# panel2.net
KiCad netlist of a schematic drawn in EAGLE
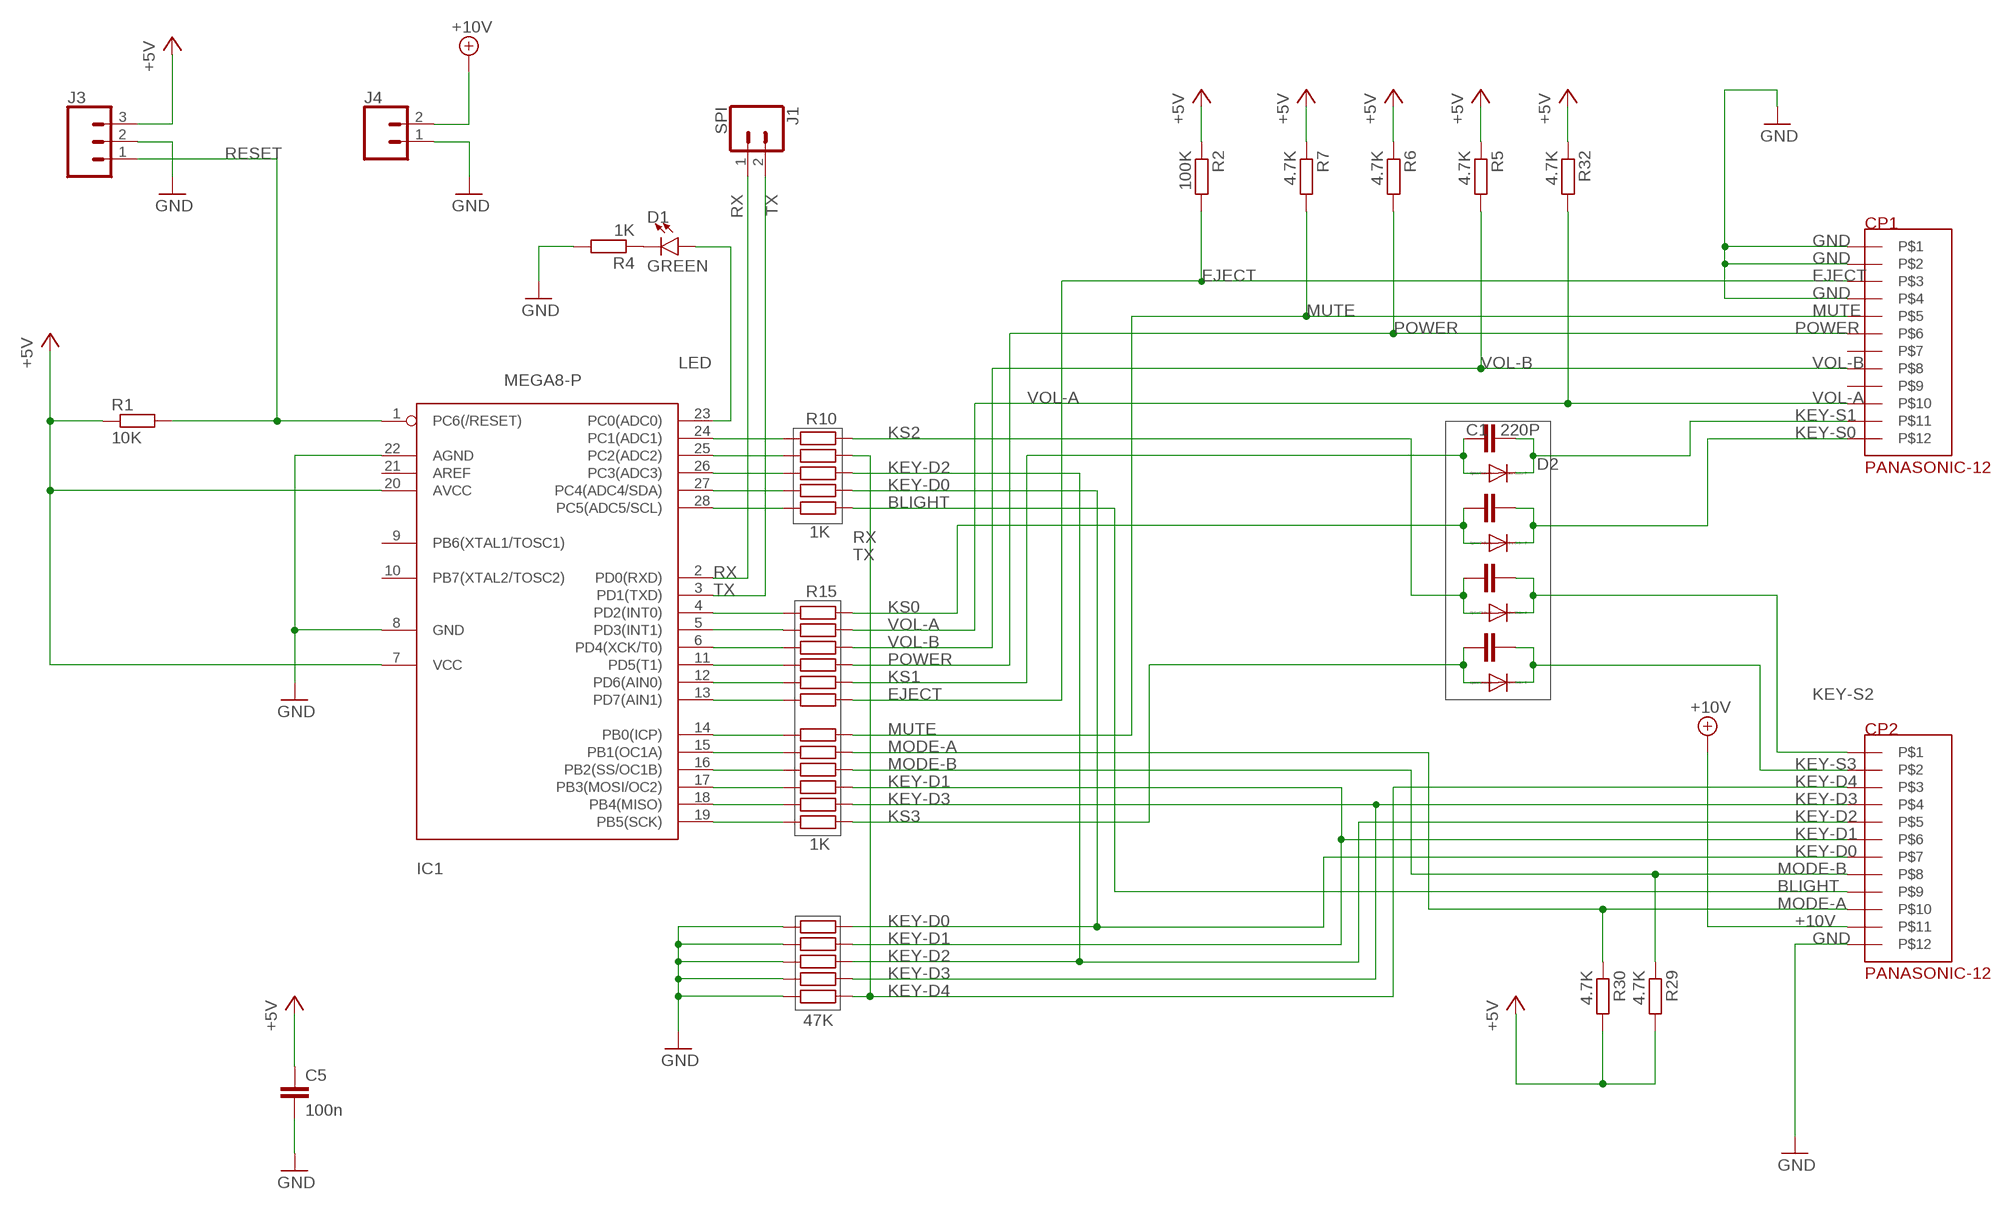
[diagram p0: schematic, sheet 1]

(export (version "E")
  (design (tool "Eeschema 10.0.6"))
  (components
    (comp (ref "C1")
      (value "220P")
      (footprint "eagle-import:C0805")
      (libsource (lib "eagle-import") (part "C-EUC0805"))
    )
    (comp (ref "C2")
      (value "220P")
      (footprint "eagle-import:C0805")
      (libsource (lib "eagle-import") (part "C-EUC0805"))
    )
    (comp (ref "C3")
      (value "220P")
      (footprint "eagle-import:C0805")
      (libsource (lib "eagle-import") (part "C-EUC0805"))
    )
    (comp (ref "C4")
      (value "220P")
      (footprint "eagle-import:C0805")
      (libsource (lib "eagle-import") (part "C-EUC0805"))
    )
    (comp (ref "C5")
      (value "100n")
      (footprint "eagle-import:C0805")
      (libsource (lib "eagle-import") (part "C-EUC0805"))
    )
    (comp (ref "CP1")
      (value "PANASONIC-12")
      (footprint "eagle-import:PANASONIC-12")
      (libsource (lib "eagle-import") (part "PANASONIC-12"))
    )
    (comp (ref "CP2")
      (value "PANASONIC-12")
      (footprint "eagle-import:PANASONIC-12")
      (libsource (lib "eagle-import") (part "PANASONIC-12"))
    )
    (comp (ref "D1")
      (value "GREEN")
      (footprint "eagle-import:LED-1206")
      (libsource (lib "eagle-import") (part "LED-GREEN1206"))
    )
    (comp (ref "D2")
      (value "1N4148DO35-10")
      (footprint "eagle-import:DO35-10")
      (libsource (lib "eagle-import") (part "1N4148DO35-10"))
    )
    (comp (ref "D3")
      (value "1N4148DO35-10")
      (footprint "eagle-import:DO35-10")
      (libsource (lib "eagle-import") (part "1N4148DO35-10"))
    )
    (comp (ref "D4")
      (value "1N4148DO35-10")
      (footprint "eagle-import:DO35-10")
      (libsource (lib "eagle-import") (part "1N4148DO35-10"))
    )
    (comp (ref "D5")
      (value "1N4148DO35-10")
      (footprint "eagle-import:DO35-10")
      (libsource (lib "eagle-import") (part "1N4148DO35-10"))
    )
    (comp (ref "IC1")
      (value "MEGA8-P")
      (footprint "eagle-import:DIL28-3")
      (libsource (lib "eagle-import") (part "MEGA8-P"))
    )
    (comp (ref "J1")
      (value "SPI")
      (footprint "eagle-import:1X02_LONGPADS")
      (libsource (lib "eagle-import") (part "CONN_02PTH3"))
    )
    (comp (ref "J3")
      (value "CONN_03LONGPADS")
      (footprint "eagle-import:1X03_LONGPADS")
      (libsource (lib "eagle-import") (part "CONN_03LONGPADS"))
    )
    (comp (ref "J4")
      (value "CONN_02LOCK_LONGPADS")
      (footprint "eagle-import:1X02_LOCK_LONGPADS")
      (libsource (lib "eagle-import") (part "CONN_02LOCK_LONGPADS"))
    )
    (comp (ref "R1")
      (value "10K")
      (footprint "eagle-import:M0805")
      (libsource (lib "eagle-import") (part "R-EU_M0805"))
    )
    (comp (ref "R2")
      (value "100K")
      (footprint "eagle-import:M0805")
      (libsource (lib "eagle-import") (part "R-EU_M0805"))
    )
    (comp (ref "R3")
      (value "47K")
      (footprint "eagle-import:0207_10")
      (libsource (lib "eagle-import") (part "R-EU_0207/10"))
    )
    (comp (ref "R4")
      (value "1K")
      (footprint "eagle-import:M0805")
      (libsource (lib "eagle-import") (part "R-EU_M0805"))
    )
    (comp (ref "R5")
      (value "4.7K")
      (footprint "eagle-import:M0805")
      (libsource (lib "eagle-import") (part "R-EU_M0805"))
    )
    (comp (ref "R6")
      (value "4.7K")
      (footprint "eagle-import:M0805")
      (libsource (lib "eagle-import") (part "R-EU_M0805"))
    )
    (comp (ref "R7")
      (value "4.7K")
      (footprint "eagle-import:M0805")
      (libsource (lib "eagle-import") (part "R-EU_M0805"))
    )
    (comp (ref "R8")
      (value "1K")
      (footprint "eagle-import:M0805")
      (libsource (lib "eagle-import") (part "R-EU_M0805"))
    )
    (comp (ref "R9")
      (value "1K")
      (footprint "eagle-import:M0805")
      (libsource (lib "eagle-import") (part "R-EU_M0805"))
    )
    (comp (ref "R10")
      (value "1K")
      (footprint "eagle-import:M0805")
      (libsource (lib "eagle-import") (part "R-EU_M0805"))
    )
    (comp (ref "R11")
      (value "1K")
      (footprint "eagle-import:M0805")
      (libsource (lib "eagle-import") (part "R-EU_M0805"))
    )
    (comp (ref "R12")
      (value "1K")
      (footprint "eagle-import:M0805")
      (libsource (lib "eagle-import") (part "R-EU_M0805"))
    )
    (comp (ref "R13")
      (value "1K")
      (footprint "eagle-import:M0805")
      (libsource (lib "eagle-import") (part "R-EU_M0805"))
    )
    (comp (ref "R14")
      (value "1K")
      (footprint "eagle-import:M0805")
      (libsource (lib "eagle-import") (part "R-EU_M0805"))
    )
    (comp (ref "R15")
      (value "1K")
      (footprint "eagle-import:M0805")
      (libsource (lib "eagle-import") (part "R-EU_M0805"))
    )
    (comp (ref "R16")
      (value "1K")
      (footprint "eagle-import:M0805")
      (libsource (lib "eagle-import") (part "R-EU_M0805"))
    )
    (comp (ref "R17")
      (value "1K")
      (footprint "eagle-import:M0805")
      (libsource (lib "eagle-import") (part "R-EU_M0805"))
    )
    (comp (ref "R18")
      (value "1K")
      (footprint "eagle-import:M0805")
      (libsource (lib "eagle-import") (part "R-EU_M0805"))
    )
    (comp (ref "R19")
      (value "1K")
      (footprint "eagle-import:M0805")
      (libsource (lib "eagle-import") (part "R-EU_M0805"))
    )
    (comp (ref "R20")
      (value "1K")
      (footprint "eagle-import:M0805")
      (libsource (lib "eagle-import") (part "R-EU_M0805"))
    )
    (comp (ref "R21")
      (value "1K")
      (footprint "eagle-import:M0805")
      (libsource (lib "eagle-import") (part "R-EU_M0805"))
    )
    (comp (ref "R22")
      (value "1K")
      (footprint "eagle-import:M0805")
      (libsource (lib "eagle-import") (part "R-EU_M0805"))
    )
    (comp (ref "R23")
      (value "1K")
      (footprint "eagle-import:M0805")
      (libsource (lib "eagle-import") (part "R-EU_M0805"))
    )
    (comp (ref "R24")
      (value "47K")
      (footprint "eagle-import:0207_10")
      (libsource (lib "eagle-import") (part "R-EU_0207/10"))
    )
    (comp (ref "R25")
      (value "47K")
      (footprint "eagle-import:0207_10")
      (libsource (lib "eagle-import") (part "R-EU_0207/10"))
    )
    (comp (ref "R28")
      (value "47K")
      (footprint "eagle-import:0207_10")
      (libsource (lib "eagle-import") (part "R-EU_0207/10"))
    )
    (comp (ref "R29")
      (value "4.7K")
      (footprint "eagle-import:M0805")
      (libsource (lib "eagle-import") (part "R-EU_M0805"))
    )
    (comp (ref "R30")
      (value "4.7K")
      (footprint "eagle-import:M0805")
      (libsource (lib "eagle-import") (part "R-EU_M0805"))
    )
    (comp (ref "R31")
      (value "1K")
      (footprint "eagle-import:M0805")
      (libsource (lib "eagle-import") (part "R-EU_M0805"))
    )
    (comp (ref "R32")
      (value "4.7K")
      (footprint "eagle-import:0207_10")
      (libsource (lib "eagle-import") (part "R-EU_0207/10"))
    )
    (comp (ref "R34")
      (value "47K")
      (footprint "eagle-import:0207_10")
      (libsource (lib "eagle-import") (part "R-EU_0207/10"))
    )
  )
  (nets
    (net (code "1") (name "+5V") (class "Default")
      (node (ref "C5") (pin "1") (pinfunction "1_1") (pintype "passive"))
      (node (ref "IC1") (pin "20") (pinfunction "AVCC_20") (pintype "bidirectional"))
      (node (ref "IC1") (pin "7") (pinfunction "VCC_7") (pintype "bidirectional"))
      (node (ref "J3") (pin "3") (pinfunction "3_3") (pintype "passive"))
      (node (ref "R1") (pin "1") (pinfunction "1_1") (pintype "passive"))
      (node (ref "R2") (pin "1") (pinfunction "1_1") (pintype "passive"))
      (node (ref "R29") (pin "2") (pinfunction "2_2") (pintype "passive"))
      (node (ref "R30") (pin "2") (pinfunction "2_2") (pintype "passive"))
      (node (ref "R32") (pin "1") (pinfunction "1_1") (pintype "passive"))
      (node (ref "R5") (pin "1") (pinfunction "1_1") (pintype "passive"))
      (node (ref "R6") (pin "1") (pinfunction "1_1") (pintype "passive"))
      (node (ref "R7") (pin "1") (pinfunction "1_1") (pintype "passive"))
    )
    (net (code "2") (name "+10V") (class "Default")
      (node (ref "CP2") (pin "P11") (pinfunction "P$11_P11") (pintype "bidirectional"))
      (node (ref "J4") (pin "2") (pinfunction "2_2") (pintype "passive"))
    )
    (net (code "3") (name "/BLIGHT") (class "Default")
      (node (ref "CP2") (pin "P9") (pinfunction "P$9_P9") (pintype "bidirectional"))
      (node (ref "R14") (pin "2") (pinfunction "2_2") (pintype "passive"))
    )
    (net (code "4") (name "/EJECT") (class "Default")
      (node (ref "CP1") (pin "P3") (pinfunction "P$3_P3") (pintype "bidirectional"))
      (node (ref "R2") (pin "2") (pinfunction "2_2") (pintype "passive"))
      (node (ref "R23") (pin "2") (pinfunction "2_2") (pintype "passive"))
    )
    (net (code "5") (name "/KEY-D0") (class "Default")
      (node (ref "CP2") (pin "P7") (pinfunction "P$7_P7") (pintype "bidirectional"))
      (node (ref "R13") (pin "2") (pinfunction "2_2") (pintype "passive"))
      (node (ref "R24") (pin "1") (pinfunction "1_1") (pintype "passive"))
    )
    (net (code "6") (name "/KEY-D1") (class "Default")
      (node (ref "CP2") (pin "P6") (pinfunction "P$6_P6") (pintype "bidirectional"))
      (node (ref "R18") (pin "2") (pinfunction "2_2") (pintype "passive"))
      (node (ref "R25") (pin "1") (pinfunction "1_1") (pintype "passive"))
    )
    (net (code "7") (name "/KEY-D2") (class "Default")
      (node (ref "CP2") (pin "P5") (pinfunction "P$5_P5") (pintype "bidirectional"))
      (node (ref "R12") (pin "2") (pinfunction "2_2") (pintype "passive"))
      (node (ref "R28") (pin "1") (pinfunction "1_1") (pintype "passive"))
    )
    (net (code "8") (name "/KEY-D3") (class "Default")
      (node (ref "CP2") (pin "P4") (pinfunction "P$4_P4") (pintype "bidirectional"))
      (node (ref "R21") (pin "2") (pinfunction "2_2") (pintype "passive"))
      (node (ref "R34") (pin "1") (pinfunction "1_1") (pintype "passive"))
    )
    (net (code "9") (name "/KEY-D4") (class "Default")
      (node (ref "CP2") (pin "P3") (pinfunction "P$3_P3") (pintype "bidirectional"))
      (node (ref "R11") (pin "2") (pinfunction "2_2") (pintype "passive"))
      (node (ref "R3") (pin "1") (pinfunction "1_1") (pintype "passive"))
    )
    (net (code "10") (name "/KEY-S0") (class "Default")
      (node (ref "C2") (pin "2") (pinfunction "2_2") (pintype "passive"))
      (node (ref "CP1") (pin "P12") (pinfunction "P$12_P12") (pintype "bidirectional"))
      (node (ref "D3") (pin "C") (pinfunction "C_C") (pintype "passive"))
    )
    (net (code "11") (name "/KEY-S1") (class "Default")
      (node (ref "C1") (pin "2") (pinfunction "2_2") (pintype "passive"))
      (node (ref "CP1") (pin "P11") (pinfunction "P$11_P11") (pintype "bidirectional"))
      (node (ref "D2") (pin "C") (pinfunction "C_C") (pintype "passive"))
    )
    (net (code "12") (name "/KEY-S2") (class "Default")
      (node (ref "C3") (pin "2") (pinfunction "2_2") (pintype "passive"))
      (node (ref "CP2") (pin "P1") (pinfunction "P$1_P1") (pintype "bidirectional"))
      (node (ref "D4") (pin "C") (pinfunction "C_C") (pintype "passive"))
    )
    (net (code "13") (name "/KEY-S3") (class "Default")
      (node (ref "C4") (pin "2") (pinfunction "2_2") (pintype "passive"))
      (node (ref "CP2") (pin "P2") (pinfunction "P$2_P2") (pintype "bidirectional"))
      (node (ref "D5") (pin "C") (pinfunction "C_C") (pintype "passive"))
    )
    (net (code "14") (name "/KS0") (class "Default")
      (node (ref "C2") (pin "1") (pinfunction "1_1") (pintype "passive"))
      (node (ref "D3") (pin "A") (pinfunction "A_A") (pintype "passive"))
      (node (ref "R15") (pin "2") (pinfunction "2_2") (pintype "passive"))
    )
    (net (code "15") (name "/KS1") (class "Default")
      (node (ref "C1") (pin "1") (pinfunction "1_1") (pintype "passive"))
      (node (ref "D2") (pin "A") (pinfunction "A_A") (pintype "passive"))
      (node (ref "R22") (pin "2") (pinfunction "2_2") (pintype "passive"))
    )
    (net (code "16") (name "/KS2") (class "Default")
      (node (ref "C3") (pin "1") (pinfunction "1_1") (pintype "passive"))
      (node (ref "D4") (pin "A") (pinfunction "A_A") (pintype "passive"))
      (node (ref "R10") (pin "2") (pinfunction "2_2") (pintype "passive"))
    )
    (net (code "17") (name "/KS3") (class "Default")
      (node (ref "C4") (pin "1") (pinfunction "1_1") (pintype "passive"))
      (node (ref "D5") (pin "A") (pinfunction "A_A") (pintype "passive"))
      (node (ref "R31") (pin "2") (pinfunction "2_2") (pintype "passive"))
    )
    (net (code "18") (name "/LED") (class "Default")
      (node (ref "D1") (pin "A") (pinfunction "A_A") (pintype "passive"))
      (node (ref "IC1") (pin "23") (pinfunction "PC0(ADC0)_23") (pintype "bidirectional"))
    )
    (net (code "19") (name "/MODE-A") (class "Default")
      (node (ref "CP2") (pin "P10") (pinfunction "P$10_P10") (pintype "bidirectional"))
      (node (ref "R20") (pin "2") (pinfunction "2_2") (pintype "passive"))
      (node (ref "R30") (pin "1") (pinfunction "1_1") (pintype "passive"))
    )
    (net (code "20") (name "/MODE-B") (class "Default")
      (node (ref "CP2") (pin "P8") (pinfunction "P$8_P8") (pintype "bidirectional"))
      (node (ref "R17") (pin "2") (pinfunction "2_2") (pintype "passive"))
      (node (ref "R29") (pin "1") (pinfunction "1_1") (pintype "passive"))
    )
    (net (code "21") (name "/MUTE") (class "Default")
      (node (ref "CP1") (pin "P5") (pinfunction "P$5_P5") (pintype "bidirectional"))
      (node (ref "R19") (pin "2") (pinfunction "2_2") (pintype "passive"))
      (node (ref "R7") (pin "2") (pinfunction "2_2") (pintype "passive"))
    )
    (net (code "22") (name "/POWER") (class "Default")
      (node (ref "CP1") (pin "P6") (pinfunction "P$6_P6") (pintype "bidirectional"))
      (node (ref "R6") (pin "2") (pinfunction "2_2") (pintype "passive"))
      (node (ref "R9") (pin "2") (pinfunction "2_2") (pintype "passive"))
    )
    (net (code "23") (name "/RESET") (class "Default")
      (node (ref "IC1") (pin "1") (pinfunction "PC6(/RESET)_1") (pintype "bidirectional"))
      (node (ref "J3") (pin "1") (pinfunction "1_1") (pintype "passive"))
      (node (ref "R1") (pin "2") (pinfunction "2_2") (pintype "passive"))
    )
    (net (code "24") (name "/RX") (class "Default")
      (node (ref "IC1") (pin "2") (pinfunction "PD0(RXD)_2") (pintype "bidirectional"))
      (node (ref "J1") (pin "1") (pinfunction "1_1") (pintype "passive"))
    )
    (net (code "25") (name "/TX") (class "Default")
      (node (ref "IC1") (pin "3") (pinfunction "PD1(TXD)_3") (pintype "bidirectional"))
      (node (ref "J1") (pin "2") (pinfunction "2_2") (pintype "passive"))
    )
    (net (code "26") (name "/VOL-A") (class "Default")
      (node (ref "CP1") (pin "P10") (pinfunction "P$10_P10") (pintype "bidirectional"))
      (node (ref "R16") (pin "2") (pinfunction "2_2") (pintype "passive"))
      (node (ref "R32") (pin "2") (pinfunction "2_2") (pintype "passive"))
    )
    (net (code "27") (name "/VOL-B") (class "Default")
      (node (ref "CP1") (pin "P8") (pinfunction "P$8_P8") (pintype "bidirectional"))
      (node (ref "R5") (pin "2") (pinfunction "2_2") (pintype "passive"))
      (node (ref "R8") (pin "2") (pinfunction "2_2") (pintype "passive"))
    )
    (net (code "28") (name "GND") (class "Default")
      (node (ref "C5") (pin "2") (pinfunction "2_2") (pintype "passive"))
      (node (ref "CP1") (pin "P1") (pinfunction "P$1_P1") (pintype "bidirectional"))
      (node (ref "CP1") (pin "P2") (pinfunction "P$2_P2") (pintype "bidirectional"))
      (node (ref "CP1") (pin "P4") (pinfunction "P$4_P4") (pintype "bidirectional"))
      (node (ref "CP2") (pin "P12") (pinfunction "P$12_P12") (pintype "bidirectional"))
      (node (ref "IC1") (pin "22") (pinfunction "AGND_22") (pintype "bidirectional"))
      (node (ref "IC1") (pin "8") (pinfunction "GND_8") (pintype "bidirectional"))
      (node (ref "J3") (pin "2") (pinfunction "2_2") (pintype "passive"))
      (node (ref "J4") (pin "1") (pinfunction "1_1") (pintype "passive"))
      (node (ref "R24") (pin "2") (pinfunction "2_2") (pintype "passive"))
      (node (ref "R25") (pin "2") (pinfunction "2_2") (pintype "passive"))
      (node (ref "R28") (pin "2") (pinfunction "2_2") (pintype "passive"))
      (node (ref "R3") (pin "2") (pinfunction "2_2") (pintype "passive"))
      (node (ref "R34") (pin "2") (pinfunction "2_2") (pintype "passive"))
      (node (ref "R4") (pin "2") (pinfunction "2_2") (pintype "passive"))
    )
    (net (code "29") (name "Net-(D1-PadC)") (class "Default")
      (node (ref "D1") (pin "C") (pinfunction "C_C") (pintype "passive"))
      (node (ref "R4") (pin "1") (pinfunction "1_1") (pintype "passive"))
    )
    (net (code "30") (name "Net-(IC1-PB0(ICP))") (class "Default")
      (node (ref "IC1") (pin "14") (pinfunction "PB0(ICP)_14") (pintype "bidirectional"))
      (node (ref "R19") (pin "1") (pinfunction "1_1") (pintype "passive"))
    )
    (net (code "31") (name "Net-(IC1-PB1(OC1A))") (class "Default")
      (node (ref "IC1") (pin "15") (pinfunction "PB1(OC1A)_15") (pintype "bidirectional"))
      (node (ref "R20") (pin "1") (pinfunction "1_1") (pintype "passive"))
    )
    (net (code "32") (name "Net-(IC1-PB2(SS{slash}OC1B))") (class "Default")
      (node (ref "IC1") (pin "16") (pinfunction "PB2(SS/OC1B)_16") (pintype "bidirectional"))
      (node (ref "R17") (pin "1") (pinfunction "1_1") (pintype "passive"))
    )
    (net (code "33") (name "Net-(IC1-PB3(MOSI{slash}OC2))") (class "Default")
      (node (ref "IC1") (pin "17") (pinfunction "PB3(MOSI/OC2)_17") (pintype "bidirectional"))
      (node (ref "R18") (pin "1") (pinfunction "1_1") (pintype "passive"))
    )
    (net (code "34") (name "Net-(IC1-PB4(MISO))") (class "Default")
      (node (ref "IC1") (pin "18") (pinfunction "PB4(MISO)_18") (pintype "bidirectional"))
      (node (ref "R21") (pin "1") (pinfunction "1_1") (pintype "passive"))
    )
    (net (code "35") (name "Net-(IC1-PB5(SCK))") (class "Default")
      (node (ref "IC1") (pin "19") (pinfunction "PB5(SCK)_19") (pintype "bidirectional"))
      (node (ref "R31") (pin "1") (pinfunction "1_1") (pintype "passive"))
    )
    (net (code "36") (name "Net-(IC1-PC1(ADC1))") (class "Default")
      (node (ref "IC1") (pin "24") (pinfunction "PC1(ADC1)_24") (pintype "bidirectional"))
      (node (ref "R10") (pin "1") (pinfunction "1_1") (pintype "passive"))
    )
    (net (code "37") (name "Net-(IC1-PC2(ADC2))") (class "Default")
      (node (ref "IC1") (pin "25") (pinfunction "PC2(ADC2)_25") (pintype "bidirectional"))
      (node (ref "R11") (pin "1") (pinfunction "1_1") (pintype "passive"))
    )
    (net (code "38") (name "Net-(IC1-PC3(ADC3))") (class "Default")
      (node (ref "IC1") (pin "26") (pinfunction "PC3(ADC3)_26") (pintype "bidirectional"))
      (node (ref "R12") (pin "1") (pinfunction "1_1") (pintype "passive"))
    )
    (net (code "39") (name "Net-(IC1-PC4(ADC4{slash}SDA))") (class "Default")
      (node (ref "IC1") (pin "27") (pinfunction "PC4(ADC4/SDA)_27") (pintype "bidirectional"))
      (node (ref "R13") (pin "1") (pinfunction "1_1") (pintype "passive"))
    )
    (net (code "40") (name "Net-(IC1-PC5(ADC5{slash}SCL))") (class "Default")
      (node (ref "IC1") (pin "28") (pinfunction "PC5(ADC5/SCL)_28") (pintype "bidirectional"))
      (node (ref "R14") (pin "1") (pinfunction "1_1") (pintype "passive"))
    )
    (net (code "41") (name "Net-(IC1-PD2(INT0))") (class "Default")
      (node (ref "IC1") (pin "4") (pinfunction "PD2(INT0)_4") (pintype "bidirectional"))
      (node (ref "R15") (pin "1") (pinfunction "1_1") (pintype "passive"))
    )
    (net (code "42") (name "Net-(IC1-PD3(INT1))") (class "Default")
      (node (ref "IC1") (pin "5") (pinfunction "PD3(INT1)_5") (pintype "bidirectional"))
      (node (ref "R16") (pin "1") (pinfunction "1_1") (pintype "passive"))
    )
    (net (code "43") (name "Net-(IC1-PD4(XCK{slash}T0))") (class "Default")
      (node (ref "IC1") (pin "6") (pinfunction "PD4(XCK/T0)_6") (pintype "bidirectional"))
      (node (ref "R8") (pin "1") (pinfunction "1_1") (pintype "passive"))
    )
    (net (code "44") (name "Net-(IC1-PD5(T1))") (class "Default")
      (node (ref "IC1") (pin "11") (pinfunction "PD5(T1)_11") (pintype "bidirectional"))
      (node (ref "R9") (pin "1") (pinfunction "1_1") (pintype "passive"))
    )
    (net (code "45") (name "Net-(IC1-PD6(AIN0))") (class "Default")
      (node (ref "IC1") (pin "12") (pinfunction "PD6(AIN0)_12") (pintype "bidirectional"))
      (node (ref "R22") (pin "1") (pinfunction "1_1") (pintype "passive"))
    )
    (net (code "46") (name "Net-(IC1-PD7(AIN1))") (class "Default")
      (node (ref "IC1") (pin "13") (pinfunction "PD7(AIN1)_13") (pintype "bidirectional"))
      (node (ref "R23") (pin "1") (pinfunction "1_1") (pintype "passive"))
    )
    (net (code "47") (name "unconnected-(CP1-P$7-PadP7)") (class "Default")
      (node (ref "CP1") (pin "P7") (pinfunction "P$7_P7") (pintype "bidirectional"))
    )
    (net (code "48") (name "unconnected-(CP1-P$9-PadP9)") (class "Default")
      (node (ref "CP1") (pin "P9") (pinfunction "P$9_P9") (pintype "bidirectional"))
    )
    (net (code "49") (name "unconnected-(IC1-AREF-Pad21)") (class "Default")
      (node (ref "IC1") (pin "21") (pinfunction "AREF_21") (pintype "bidirectional"))
    )
    (net (code "50") (name "unconnected-(IC1-PB6(XTAL1{slash}TOSC1)-Pad9)") (class "Default")
      (node (ref "IC1") (pin "9") (pinfunction "PB6(XTAL1/TOSC1)_9") (pintype "bidirectional"))
    )
    (net (code "51") (name "unconnected-(IC1-PB7(XTAL2{slash}TOSC2)-Pad10)") (class "Default")
      (node (ref "IC1") (pin "10") (pinfunction "PB7(XTAL2/TOSC2)_10") (pintype "bidirectional"))
    )
  )
)
